# Narrow_AAA_sensor_v1_1.net
KiCad netlist of a schematic drawn in EAGLE
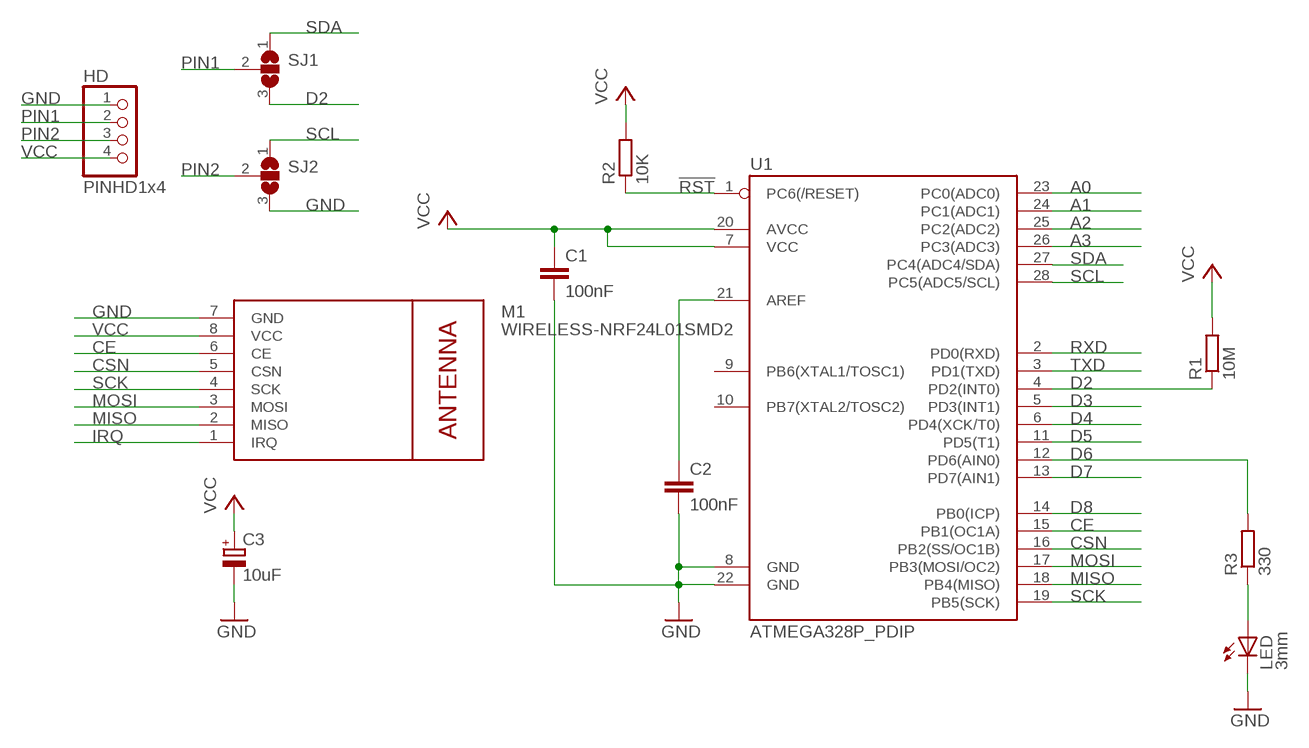
[diagram p0: schematic, sheet 1]

(export (version "E")
  (design (tool "Eeschema 10.0.6"))
  (components
    (comp (ref "C1")
      (value "100nF")
      (footprint "eagle-import:C025-025X050")
      (libsource (lib "eagle-import") (part "C-EU025-025X050"))
    )
    (comp (ref "C2")
      (value "100nF")
      (footprint "eagle-import:C025-025X050")
      (libsource (lib "eagle-import") (part "C-EU025-025X050"))
    )
    (comp (ref "C3")
      (value "10uF")
      (footprint "eagle-import:E2,5-5")
      (libsource (lib "eagle-import") (part "CPOL-EUE2.5-5"))
    )
    (comp (ref "HD")
      (value "PINHD1x4")
      (footprint "eagle-import:1X04")
      (libsource (lib "eagle-import") (part "PINHD-1X4"))
    )
    (comp (ref "LED")
      (value "3mm")
      (footprint "eagle-import:LED3MM")
      (libsource (lib "eagle-import") (part "LED3MM"))
    )
    (comp (ref "M1")
      (value "WIRELESS-NRF24L01SMD2")
      (footprint "eagle-import:WIRELESS-NRF24L01-SMD-2")
      (libsource (lib "eagle-import") (part "WIRELESS-NRF24L01SMD2"))
    )
    (comp (ref "R1")
      (value "10M")
      (footprint "eagle-import:0204_7")
      (libsource (lib "eagle-import") (part "R-EU_0204/7"))
    )
    (comp (ref "R2")
      (value "10K")
      (footprint "eagle-import:0204_7")
      (libsource (lib "eagle-import") (part "R-EU_0204/7"))
    )
    (comp (ref "R3")
      (value "330")
      (footprint "eagle-import:0204_7")
      (libsource (lib "eagle-import") (part "R-EU_0204/7"))
    )
    (comp (ref "SJ1")
      (value "SJ2W")
      (footprint "eagle-import:SJ_2")
      (libsource (lib "eagle-import") (part "SJ2W"))
    )
    (comp (ref "SJ2")
      (value "SJ2W")
      (footprint "eagle-import:SJ_2")
      (libsource (lib "eagle-import") (part "SJ2W"))
    )
    (comp (ref "U1")
      (value "ATMEGA328P_PDIP")
      (footprint "eagle-import:DIL28-3")
      (libsource (lib "eagle-import") (part "ATMEGA328P_PDIP"))
    )
  )
  (nets
    (net (code "1") (name "/A0") (class "Default")
      (node (ref "U1") (pin "23") (pinfunction "PC0(ADC0)_23") (pintype "bidirectional"))
    )
    (net (code "2") (name "/A1") (class "Default")
      (node (ref "U1") (pin "24") (pinfunction "PC1(ADC1)_24") (pintype "bidirectional"))
    )
    (net (code "3") (name "/A2") (class "Default")
      (node (ref "U1") (pin "25") (pinfunction "PC2(ADC2)_25") (pintype "bidirectional"))
    )
    (net (code "4") (name "/A3") (class "Default")
      (node (ref "U1") (pin "26") (pinfunction "PC3(ADC3)_26") (pintype "bidirectional"))
    )
    (net (code "5") (name "/CE") (class "Default")
      (node (ref "M1") (pin "6") (pinfunction "CE_6") (pintype "bidirectional"))
      (node (ref "U1") (pin "15") (pinfunction "PB1(OC1A)_15") (pintype "bidirectional"))
    )
    (net (code "6") (name "/CSN") (class "Default")
      (node (ref "M1") (pin "5") (pinfunction "CSN_5") (pintype "bidirectional"))
      (node (ref "U1") (pin "16") (pinfunction "PB2(SS/OC1B)_16") (pintype "bidirectional"))
    )
    (net (code "7") (name "/D2") (class "Default")
      (node (ref "R1") (pin "1") (pinfunction "1_1") (pintype "passive"))
      (node (ref "SJ1") (pin "3") (pinfunction "3_3") (pintype "passive"))
      (node (ref "U1") (pin "4") (pinfunction "PD2(INT0)_4") (pintype "bidirectional"))
    )
    (net (code "8") (name "/D3") (class "Default")
      (node (ref "U1") (pin "5") (pinfunction "PD3(INT1)_5") (pintype "bidirectional"))
    )
    (net (code "9") (name "/D4") (class "Default")
      (node (ref "U1") (pin "6") (pinfunction "PD4(XCK/T0)_6") (pintype "bidirectional"))
    )
    (net (code "10") (name "/D5") (class "Default")
      (node (ref "U1") (pin "11") (pinfunction "PD5(T1)_11") (pintype "bidirectional"))
    )
    (net (code "11") (name "/D6") (class "Default")
      (node (ref "R3") (pin "2") (pinfunction "2_2") (pintype "passive"))
      (node (ref "U1") (pin "12") (pinfunction "PD6(AIN0)_12") (pintype "bidirectional"))
    )
    (net (code "12") (name "/D7") (class "Default")
      (node (ref "U1") (pin "13") (pinfunction "PD7(AIN1)_13") (pintype "bidirectional"))
    )
    (net (code "13") (name "/D8") (class "Default")
      (node (ref "U1") (pin "14") (pinfunction "PB0(ICP)_14") (pintype "bidirectional"))
    )
    (net (code "14") (name "/IRQ") (class "Default")
      (node (ref "M1") (pin "1") (pinfunction "IRQ_1") (pintype "bidirectional"))
    )
    (net (code "15") (name "/MISO") (class "Default")
      (node (ref "M1") (pin "2") (pinfunction "MISO_2") (pintype "bidirectional"))
      (node (ref "U1") (pin "18") (pinfunction "PB4(MISO)_18") (pintype "bidirectional"))
    )
    (net (code "16") (name "/MOSI") (class "Default")
      (node (ref "M1") (pin "3") (pinfunction "MOSI_3") (pintype "bidirectional"))
      (node (ref "U1") (pin "17") (pinfunction "PB3(MOSI/OC2)_17") (pintype "bidirectional"))
    )
    (net (code "17") (name "/PIN1") (class "Default")
      (node (ref "HD") (pin "2") (pinfunction "2_2") (pintype "passive"))
      (node (ref "SJ1") (pin "2") (pinfunction "2_2") (pintype "passive"))
    )
    (net (code "18") (name "/PIN2") (class "Default")
      (node (ref "HD") (pin "3") (pinfunction "3_3") (pintype "passive"))
      (node (ref "SJ2") (pin "2") (pinfunction "2_2") (pintype "passive"))
    )
    (net (code "19") (name "/RXD") (class "Default")
      (node (ref "U1") (pin "2") (pinfunction "PD0(RXD)_2") (pintype "bidirectional"))
    )
    (net (code "20") (name "/SCK") (class "Default")
      (node (ref "M1") (pin "4") (pinfunction "SCK_4") (pintype "bidirectional"))
      (node (ref "U1") (pin "19") (pinfunction "PB5(SCK)_19") (pintype "bidirectional"))
    )
    (net (code "21") (name "/SCL") (class "Default")
      (node (ref "SJ2") (pin "1") (pinfunction "1_1") (pintype "passive"))
      (node (ref "U1") (pin "28") (pinfunction "PC5(ADC5/SCL)_28") (pintype "bidirectional"))
    )
    (net (code "22") (name "/SDA") (class "Default")
      (node (ref "SJ1") (pin "1") (pinfunction "1_1") (pintype "passive"))
      (node (ref "U1") (pin "27") (pinfunction "PC4(ADC4/SDA)_27") (pintype "bidirectional"))
    )
    (net (code "23") (name "/TXD") (class "Default")
      (node (ref "U1") (pin "3") (pinfunction "PD1(TXD)_3") (pintype "bidirectional"))
    )
    (net (code "24") (name "/~{RST}") (class "Default")
      (node (ref "R2") (pin "1") (pinfunction "1_1") (pintype "passive"))
      (node (ref "U1") (pin "1") (pinfunction "PC6(/RESET)_1") (pintype "bidirectional"))
    )
    (net (code "25") (name "GND") (class "Default")
      (node (ref "C1") (pin "2") (pinfunction "2_2") (pintype "passive"))
      (node (ref "C2") (pin "2") (pinfunction "2_2") (pintype "passive"))
      (node (ref "C3") (pin "-") (pinfunction "-_-") (pintype "passive"))
      (node (ref "HD") (pin "1") (pinfunction "1_1") (pintype "passive"))
      (node (ref "LED") (pin "K") (pinfunction "C_K") (pintype "passive"))
      (node (ref "M1") (pin "7") (pinfunction "GND_7") (pintype "power_in"))
      (node (ref "SJ2") (pin "3") (pinfunction "3_3") (pintype "passive"))
      (node (ref "U1") (pin "22") (pinfunction "GND_22") (pintype "bidirectional"))
      (node (ref "U1") (pin "8") (pinfunction "GND_8") (pintype "bidirectional"))
    )
    (net (code "26") (name "Net-(LED-PadA)") (class "Default")
      (node (ref "LED") (pin "A") (pinfunction "A_A") (pintype "passive"))
      (node (ref "R3") (pin "1") (pinfunction "1_1") (pintype "passive"))
    )
    (net (code "27") (name "Net-(U1-AREF)") (class "Default")
      (node (ref "C2") (pin "1") (pinfunction "1_1") (pintype "passive"))
      (node (ref "U1") (pin "21") (pinfunction "AREF_21") (pintype "bidirectional"))
    )
    (net (code "28") (name "VCC") (class "Default")
      (node (ref "C1") (pin "1") (pinfunction "1_1") (pintype "passive"))
      (node (ref "C3") (pin "+") (pinfunction "+_+") (pintype "passive"))
      (node (ref "HD") (pin "4") (pinfunction "4_4") (pintype "passive"))
      (node (ref "M1") (pin "8") (pinfunction "VCC_8") (pintype "power_in"))
      (node (ref "R1") (pin "2") (pinfunction "2_2") (pintype "passive"))
      (node (ref "R2") (pin "2") (pinfunction "2_2") (pintype "passive"))
      (node (ref "U1") (pin "20") (pinfunction "AVCC_20") (pintype "bidirectional"))
      (node (ref "U1") (pin "7") (pinfunction "VCC_7") (pintype "bidirectional"))
    )
    (net (code "29") (name "unconnected-(U1-PB6(XTAL1{slash}TOSC1)-Pad9)") (class "Default")
      (node (ref "U1") (pin "9") (pinfunction "PB6(XTAL1/TOSC1)_9") (pintype "bidirectional"))
    )
    (net (code "30") (name "unconnected-(U1-PB7(XTAL2{slash}TOSC2)-Pad10)") (class "Default")
      (node (ref "U1") (pin "10") (pinfunction "PB7(XTAL2/TOSC2)_10") (pintype "bidirectional"))
    )
  )
)
